# Sheet2.net
KiCad netlist of a schematic drawn in Altium Designer
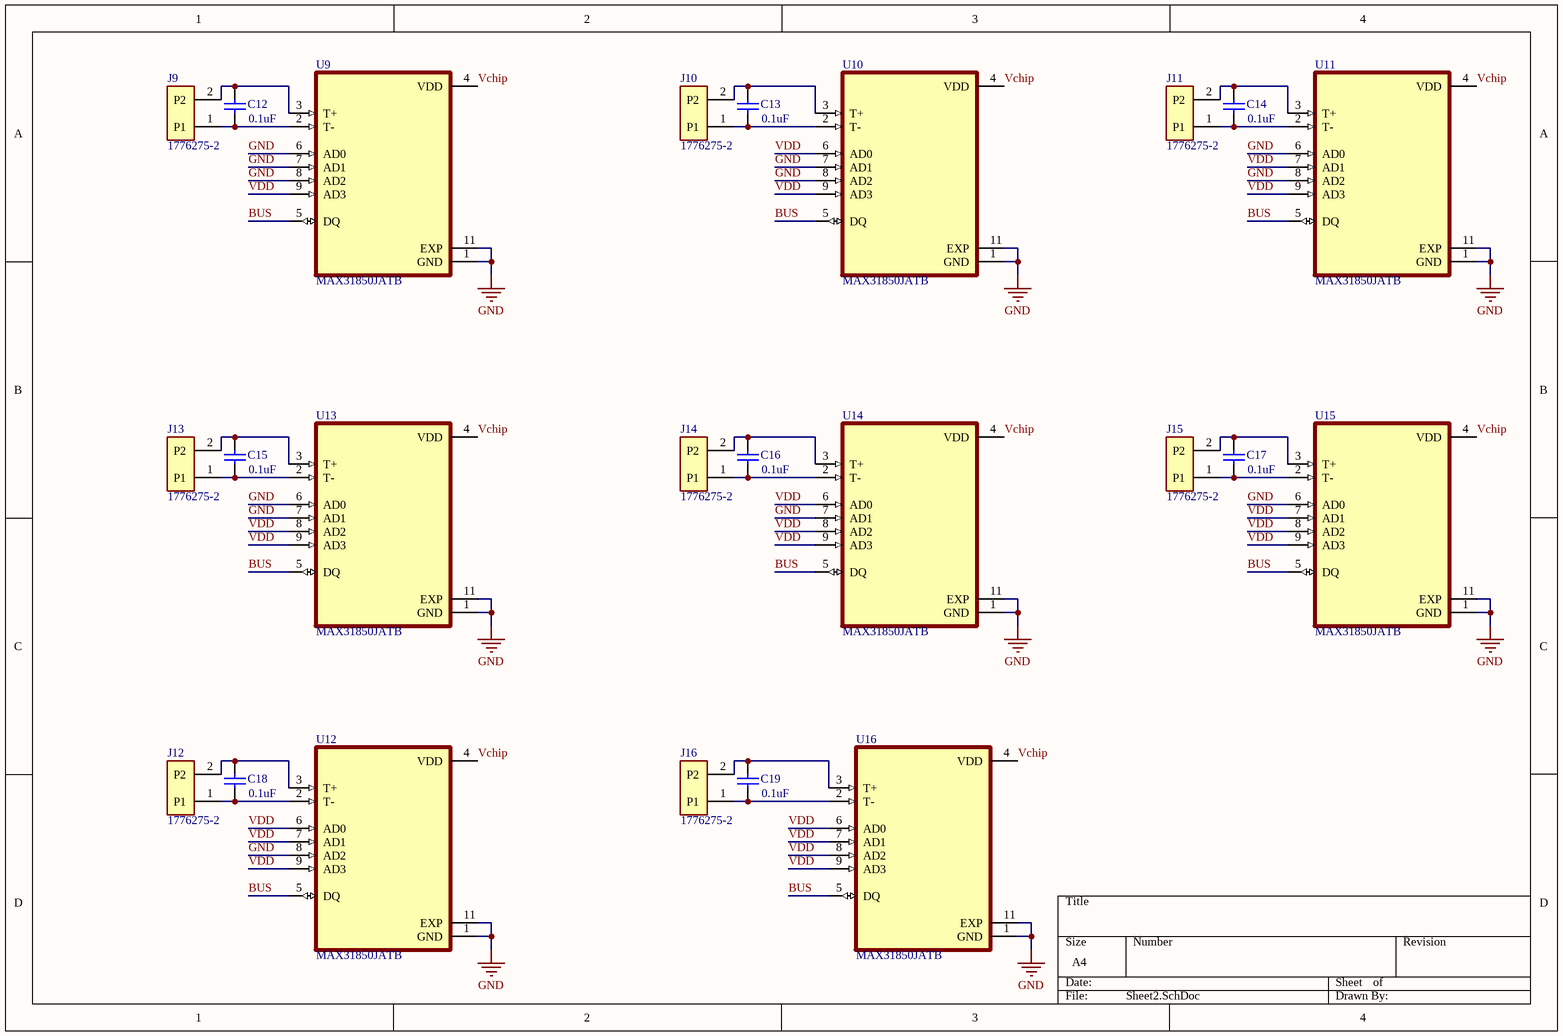
[diagram p0: Sheet2.SchDoc]

(export (version "E")
  (design (tool "Eeschema 10.0.6"))
  (components
    (comp (ref "C12")
      (value "0.1uF")
      (footprint "1608[0603]")
      (description "Capacitor (Semiconductor SIM Model)")
      (fields (field (name "PUBLISHER") "Altium Limited"))
      (libsource (lib "Miscellaneous Devices") (part "Cap Semi"))
    )
    (comp (ref "C13")
      (value "0.1uF")
      (footprint "1608[0603]")
      (description "Capacitor (Semiconductor SIM Model)")
      (fields (field (name "PUBLISHER") "Altium Limited"))
      (libsource (lib "Miscellaneous Devices") (part "Cap Semi"))
    )
    (comp (ref "C14")
      (value "0.1uF")
      (footprint "1608[0603]")
      (description "Capacitor (Semiconductor SIM Model)")
      (fields (field (name "PUBLISHER") "Altium Limited"))
      (libsource (lib "Miscellaneous Devices") (part "Cap Semi"))
    )
    (comp (ref "C15")
      (value "0.1uF")
      (footprint "1608[0603]")
      (description "Capacitor (Semiconductor SIM Model)")
      (fields (field (name "PUBLISHER") "Altium Limited"))
      (libsource (lib "Miscellaneous Devices") (part "Cap Semi"))
    )
    (comp (ref "C16")
      (value "0.1uF")
      (footprint "1608[0603]")
      (description "Capacitor (Semiconductor SIM Model)")
      (fields (field (name "PUBLISHER") "Altium Limited"))
      (libsource (lib "Miscellaneous Devices") (part "Cap Semi"))
    )
    (comp (ref "C17")
      (value "0.1uF")
      (footprint "1608[0603]")
      (description "Capacitor (Semiconductor SIM Model)")
      (fields (field (name "PUBLISHER") "Altium Limited"))
      (libsource (lib "Miscellaneous Devices") (part "Cap Semi"))
    )
    (comp (ref "C18")
      (value "0.1uF")
      (footprint "1608[0603]")
      (description "Capacitor (Semiconductor SIM Model)")
      (fields (field (name "PUBLISHER") "Altium Limited"))
      (libsource (lib "Miscellaneous Devices") (part "Cap Semi"))
    )
    (comp (ref "C19")
      (value "0.1uF")
      (footprint "1608[0603]")
      (description "Capacitor (Semiconductor SIM Model)")
      (fields (field (name "PUBLISHER") "Altium Limited"))
      (libsource (lib "Miscellaneous Devices") (part "Cap Semi"))
    )
    (comp (ref "J9")
      (value "1776275-2")
      (footprint "1776275-2:TE_1776275-2")
      (description "TERM BLOCK 2POS SIDE ENT 3.5MM")
      (fields (field (name "MF") "{'manufacturer': u'TE Connectivity'}"))
      (libsource (lib "*") (part "1776275-2"))
    )
    (comp (ref "J10")
      (value "1776275-2")
      (footprint "1776275-2:TE_1776275-2")
      (description "TERM BLOCK 2POS SIDE ENT 3.5MM")
      (fields (field (name "MF") "{'manufacturer': u'TE Connectivity'}"))
      (libsource (lib "*") (part "1776275-2"))
    )
    (comp (ref "J11")
      (value "1776275-2")
      (footprint "1776275-2:TE_1776275-2")
      (description "TERM BLOCK 2POS SIDE ENT 3.5MM")
      (fields (field (name "MF") "{'manufacturer': u'TE Connectivity'}"))
      (libsource (lib "*") (part "1776275-2"))
    )
    (comp (ref "J12")
      (value "1776275-2")
      (footprint "1776275-2:TE_1776275-2")
      (description "TERM BLOCK 2POS SIDE ENT 3.5MM")
      (fields (field (name "MF") "{'manufacturer': u'TE Connectivity'}"))
      (libsource (lib "*") (part "1776275-2"))
    )
    (comp (ref "J13")
      (value "1776275-2")
      (footprint "1776275-2:TE_1776275-2")
      (description "TERM BLOCK 2POS SIDE ENT 3.5MM")
      (fields (field (name "MF") "{'manufacturer': u'TE Connectivity'}"))
      (libsource (lib "*") (part "1776275-2"))
    )
    (comp (ref "J14")
      (value "1776275-2")
      (footprint "1776275-2:TE_1776275-2")
      (description "TERM BLOCK 2POS SIDE ENT 3.5MM")
      (fields (field (name "MF") "{'manufacturer': u'TE Connectivity'}"))
      (libsource (lib "*") (part "1776275-2"))
    )
    (comp (ref "J15")
      (value "1776275-2")
      (footprint "1776275-2:TE_1776275-2")
      (description "TERM BLOCK 2POS SIDE ENT 3.5MM")
      (fields (field (name "MF") "{'manufacturer': u'TE Connectivity'}"))
      (libsource (lib "*") (part "1776275-2"))
    )
    (comp (ref "J16")
      (value "1776275-2")
      (footprint "1776275-2:TE_1776275-2")
      (description "TERM BLOCK 2POS SIDE ENT 3.5MM")
      (fields (field (name "MF") "{'manufacturer': u'TE Connectivity'}"))
      (libsource (lib "*") (part "1776275-2"))
    )
    (comp (ref "U9")
      (value "MAX31850JATB")
      (footprint "MAX31850JATB+:SON50P300X400X80-11N")
      (description "None")
      (fields (field (name "MF") "{'manufacturer': u'Maxim Integrated'}"))
      (libsource (lib "*") (part "MAX31850JATB"))
    )
    (comp (ref "U10")
      (value "MAX31850JATB")
      (footprint "MAX31850JATB+:SON50P300X400X80-11N")
      (description "None")
      (fields (field (name "MF") "{'manufacturer': u'Maxim Integrated'}"))
      (libsource (lib "*") (part "MAX31850JATB"))
    )
    (comp (ref "U11")
      (value "MAX31850JATB")
      (footprint "MAX31850JATB+:SON50P300X400X80-11N")
      (description "None")
      (fields (field (name "MF") "{'manufacturer': u'Maxim Integrated'}"))
      (libsource (lib "*") (part "MAX31850JATB"))
    )
    (comp (ref "U12")
      (value "MAX31850JATB")
      (footprint "MAX31850JATB+:SON50P300X400X80-11N")
      (description "None")
      (fields (field (name "MF") "{'manufacturer': u'Maxim Integrated'}"))
      (libsource (lib "*") (part "MAX31850JATB"))
    )
    (comp (ref "U13")
      (value "MAX31850JATB")
      (footprint "MAX31850JATB+:SON50P300X400X80-11N")
      (description "None")
      (fields (field (name "MF") "{'manufacturer': u'Maxim Integrated'}"))
      (libsource (lib "*") (part "MAX31850JATB"))
    )
    (comp (ref "U14")
      (value "MAX31850JATB")
      (footprint "MAX31850JATB+:SON50P300X400X80-11N")
      (description "None")
      (fields (field (name "MF") "{'manufacturer': u'Maxim Integrated'}"))
      (libsource (lib "*") (part "MAX31850JATB"))
    )
    (comp (ref "U15")
      (value "MAX31850JATB")
      (footprint "MAX31850JATB+:SON50P300X400X80-11N")
      (description "None")
      (fields (field (name "MF") "{'manufacturer': u'Maxim Integrated'}"))
      (libsource (lib "*") (part "MAX31850JATB"))
    )
    (comp (ref "U16")
      (value "MAX31850JATB")
      (footprint "MAX31850JATB+:SON50P300X400X80-11N")
      (description "None")
      (fields (field (name "MF") "{'manufacturer': u'Maxim Integrated'}"))
      (libsource (lib "*") (part "MAX31850JATB"))
    )
  )
  (nets
    (net (code "1") (name "/BUS") (class "Default")
      (node (ref "U10") (pin "5") (pinfunction "DQ_5") (pintype "bidirectional"))
      (node (ref "U11") (pin "5") (pinfunction "DQ_5") (pintype "bidirectional"))
      (node (ref "U12") (pin "5") (pinfunction "DQ_5") (pintype "bidirectional"))
      (node (ref "U13") (pin "5") (pinfunction "DQ_5") (pintype "bidirectional"))
      (node (ref "U14") (pin "5") (pinfunction "DQ_5") (pintype "bidirectional"))
      (node (ref "U15") (pin "5") (pinfunction "DQ_5") (pintype "bidirectional"))
      (node (ref "U16") (pin "5") (pinfunction "DQ_5") (pintype "bidirectional"))
      (node (ref "U9") (pin "5") (pinfunction "DQ_5") (pintype "bidirectional"))
    )
    (net (code "2") (name "/VDD") (class "Default")
      (node (ref "U10") (pin "6") (pinfunction "AD0_6") (pintype "input"))
      (node (ref "U10") (pin "9") (pinfunction "AD3_9") (pintype "input"))
      (node (ref "U11") (pin "7") (pinfunction "AD1_7") (pintype "input"))
      (node (ref "U11") (pin "9") (pinfunction "AD3_9") (pintype "input"))
      (node (ref "U12") (pin "6") (pinfunction "AD0_6") (pintype "input"))
      (node (ref "U12") (pin "7") (pinfunction "AD1_7") (pintype "input"))
      (node (ref "U12") (pin "9") (pinfunction "AD3_9") (pintype "input"))
      (node (ref "U13") (pin "8") (pinfunction "AD2_8") (pintype "input"))
      (node (ref "U13") (pin "9") (pinfunction "AD3_9") (pintype "input"))
      (node (ref "U14") (pin "6") (pinfunction "AD0_6") (pintype "input"))
      (node (ref "U14") (pin "8") (pinfunction "AD2_8") (pintype "input"))
      (node (ref "U14") (pin "9") (pinfunction "AD3_9") (pintype "input"))
      (node (ref "U15") (pin "7") (pinfunction "AD1_7") (pintype "input"))
      (node (ref "U15") (pin "8") (pinfunction "AD2_8") (pintype "input"))
      (node (ref "U15") (pin "9") (pinfunction "AD3_9") (pintype "input"))
      (node (ref "U16") (pin "6") (pinfunction "AD0_6") (pintype "input"))
      (node (ref "U16") (pin "7") (pinfunction "AD1_7") (pintype "input"))
      (node (ref "U16") (pin "8") (pinfunction "AD2_8") (pintype "input"))
      (node (ref "U16") (pin "9") (pinfunction "AD3_9") (pintype "input"))
      (node (ref "U9") (pin "9") (pinfunction "AD3_9") (pintype "input"))
    )
    (net (code "3") (name "/Vchip") (class "Default")
      (node (ref "U10") (pin "4") (pinfunction "VDD_4") (pintype "power_in"))
      (node (ref "U11") (pin "4") (pinfunction "VDD_4") (pintype "power_in"))
      (node (ref "U12") (pin "4") (pinfunction "VDD_4") (pintype "power_in"))
      (node (ref "U13") (pin "4") (pinfunction "VDD_4") (pintype "power_in"))
      (node (ref "U14") (pin "4") (pinfunction "VDD_4") (pintype "power_in"))
      (node (ref "U15") (pin "4") (pinfunction "VDD_4") (pintype "power_in"))
      (node (ref "U16") (pin "4") (pinfunction "VDD_4") (pintype "power_in"))
      (node (ref "U9") (pin "4") (pinfunction "VDD_4") (pintype "power_in"))
    )
    (net (code "4") (name "GND") (class "Default")
      (node (ref "U10") (pin "1") (pinfunction "GND_1") (pintype "power_in"))
      (node (ref "U10") (pin "11") (pinfunction "EXP_11") (pintype "power_in"))
      (node (ref "U10") (pin "7") (pinfunction "AD1_7") (pintype "input"))
      (node (ref "U10") (pin "8") (pinfunction "AD2_8") (pintype "input"))
      (node (ref "U11") (pin "1") (pinfunction "GND_1") (pintype "power_in"))
      (node (ref "U11") (pin "11") (pinfunction "EXP_11") (pintype "power_in"))
      (node (ref "U11") (pin "6") (pinfunction "AD0_6") (pintype "input"))
      (node (ref "U11") (pin "8") (pinfunction "AD2_8") (pintype "input"))
      (node (ref "U12") (pin "1") (pinfunction "GND_1") (pintype "power_in"))
      (node (ref "U12") (pin "11") (pinfunction "EXP_11") (pintype "power_in"))
      (node (ref "U12") (pin "8") (pinfunction "AD2_8") (pintype "input"))
      (node (ref "U13") (pin "1") (pinfunction "GND_1") (pintype "power_in"))
      (node (ref "U13") (pin "11") (pinfunction "EXP_11") (pintype "power_in"))
      (node (ref "U13") (pin "6") (pinfunction "AD0_6") (pintype "input"))
      (node (ref "U13") (pin "7") (pinfunction "AD1_7") (pintype "input"))
      (node (ref "U14") (pin "1") (pinfunction "GND_1") (pintype "power_in"))
      (node (ref "U14") (pin "11") (pinfunction "EXP_11") (pintype "power_in"))
      (node (ref "U14") (pin "7") (pinfunction "AD1_7") (pintype "input"))
      (node (ref "U15") (pin "1") (pinfunction "GND_1") (pintype "power_in"))
      (node (ref "U15") (pin "11") (pinfunction "EXP_11") (pintype "power_in"))
      (node (ref "U15") (pin "6") (pinfunction "AD0_6") (pintype "input"))
      (node (ref "U16") (pin "1") (pinfunction "GND_1") (pintype "power_in"))
      (node (ref "U16") (pin "11") (pinfunction "EXP_11") (pintype "power_in"))
      (node (ref "U9") (pin "1") (pinfunction "GND_1") (pintype "power_in"))
      (node (ref "U9") (pin "11") (pinfunction "EXP_11") (pintype "power_in"))
      (node (ref "U9") (pin "6") (pinfunction "AD0_6") (pintype "input"))
      (node (ref "U9") (pin "7") (pinfunction "AD1_7") (pintype "input"))
      (node (ref "U9") (pin "8") (pinfunction "AD2_8") (pintype "input"))
    )
    (net (code "5") (name "Net-(J9-P1)") (class "Default")
      (node (ref "C12") (pin "1") (pinfunction "1_1") (pintype "passive"))
      (node (ref "J9") (pin "1") (pinfunction "P1_1") (pintype "passive"))
      (node (ref "U9") (pin "2") (pinfunction "T-_2") (pintype "input"))
    )
    (net (code "6") (name "Net-(J9-P2)") (class "Default")
      (node (ref "C12") (pin "2") (pinfunction "2_2") (pintype "passive"))
      (node (ref "J9") (pin "2") (pinfunction "P2_2") (pintype "passive"))
      (node (ref "U9") (pin "3") (pinfunction "T+_3") (pintype "input"))
    )
    (net (code "7") (name "Net-(J10-P1)") (class "Default")
      (node (ref "C13") (pin "1") (pinfunction "1_1") (pintype "passive"))
      (node (ref "J10") (pin "1") (pinfunction "P1_1") (pintype "passive"))
      (node (ref "U10") (pin "2") (pinfunction "T-_2") (pintype "input"))
    )
    (net (code "8") (name "Net-(J10-P2)") (class "Default")
      (node (ref "C13") (pin "2") (pinfunction "2_2") (pintype "passive"))
      (node (ref "J10") (pin "2") (pinfunction "P2_2") (pintype "passive"))
      (node (ref "U10") (pin "3") (pinfunction "T+_3") (pintype "input"))
    )
    (net (code "9") (name "Net-(J11-P1)") (class "Default")
      (node (ref "C14") (pin "1") (pinfunction "1_1") (pintype "passive"))
      (node (ref "J11") (pin "1") (pinfunction "P1_1") (pintype "passive"))
      (node (ref "U11") (pin "2") (pinfunction "T-_2") (pintype "input"))
    )
    (net (code "10") (name "Net-(J11-P2)") (class "Default")
      (node (ref "C14") (pin "2") (pinfunction "2_2") (pintype "passive"))
      (node (ref "J11") (pin "2") (pinfunction "P2_2") (pintype "passive"))
      (node (ref "U11") (pin "3") (pinfunction "T+_3") (pintype "input"))
    )
    (net (code "11") (name "Net-(J12-P1)") (class "Default")
      (node (ref "C18") (pin "1") (pinfunction "1_1") (pintype "passive"))
      (node (ref "J12") (pin "1") (pinfunction "P1_1") (pintype "passive"))
      (node (ref "U12") (pin "2") (pinfunction "T-_2") (pintype "input"))
    )
    (net (code "12") (name "Net-(J12-P2)") (class "Default")
      (node (ref "C18") (pin "2") (pinfunction "2_2") (pintype "passive"))
      (node (ref "J12") (pin "2") (pinfunction "P2_2") (pintype "passive"))
      (node (ref "U12") (pin "3") (pinfunction "T+_3") (pintype "input"))
    )
    (net (code "13") (name "Net-(J13-P1)") (class "Default")
      (node (ref "C15") (pin "1") (pinfunction "1_1") (pintype "passive"))
      (node (ref "J13") (pin "1") (pinfunction "P1_1") (pintype "passive"))
      (node (ref "U13") (pin "2") (pinfunction "T-_2") (pintype "input"))
    )
    (net (code "14") (name "Net-(J13-P2)") (class "Default")
      (node (ref "C15") (pin "2") (pinfunction "2_2") (pintype "passive"))
      (node (ref "J13") (pin "2") (pinfunction "P2_2") (pintype "passive"))
      (node (ref "U13") (pin "3") (pinfunction "T+_3") (pintype "input"))
    )
    (net (code "15") (name "Net-(J14-P1)") (class "Default")
      (node (ref "C16") (pin "1") (pinfunction "1_1") (pintype "passive"))
      (node (ref "J14") (pin "1") (pinfunction "P1_1") (pintype "passive"))
      (node (ref "U14") (pin "2") (pinfunction "T-_2") (pintype "input"))
    )
    (net (code "16") (name "Net-(J14-P2)") (class "Default")
      (node (ref "C16") (pin "2") (pinfunction "2_2") (pintype "passive"))
      (node (ref "J14") (pin "2") (pinfunction "P2_2") (pintype "passive"))
      (node (ref "U14") (pin "3") (pinfunction "T+_3") (pintype "input"))
    )
    (net (code "17") (name "Net-(J15-P1)") (class "Default")
      (node (ref "C17") (pin "1") (pinfunction "1_1") (pintype "passive"))
      (node (ref "J15") (pin "1") (pinfunction "P1_1") (pintype "passive"))
      (node (ref "U15") (pin "2") (pinfunction "T-_2") (pintype "input"))
    )
    (net (code "18") (name "Net-(J15-P2)") (class "Default")
      (node (ref "C17") (pin "2") (pinfunction "2_2") (pintype "passive"))
      (node (ref "J15") (pin "2") (pinfunction "P2_2") (pintype "passive"))
      (node (ref "U15") (pin "3") (pinfunction "T+_3") (pintype "input"))
    )
    (net (code "19") (name "Net-(J16-P1)") (class "Default")
      (node (ref "C19") (pin "1") (pinfunction "1_1") (pintype "passive"))
      (node (ref "J16") (pin "1") (pinfunction "P1_1") (pintype "passive"))
      (node (ref "U16") (pin "2") (pinfunction "T-_2") (pintype "input"))
    )
    (net (code "20") (name "Net-(J16-P2)") (class "Default")
      (node (ref "C19") (pin "2") (pinfunction "2_2") (pintype "passive"))
      (node (ref "J16") (pin "2") (pinfunction "P2_2") (pintype "passive"))
      (node (ref "U16") (pin "3") (pinfunction "T+_3") (pintype "input"))
    )
  )
)
